# IRC2K16.net
KiCad netlist of a schematic drawn in EAGLE
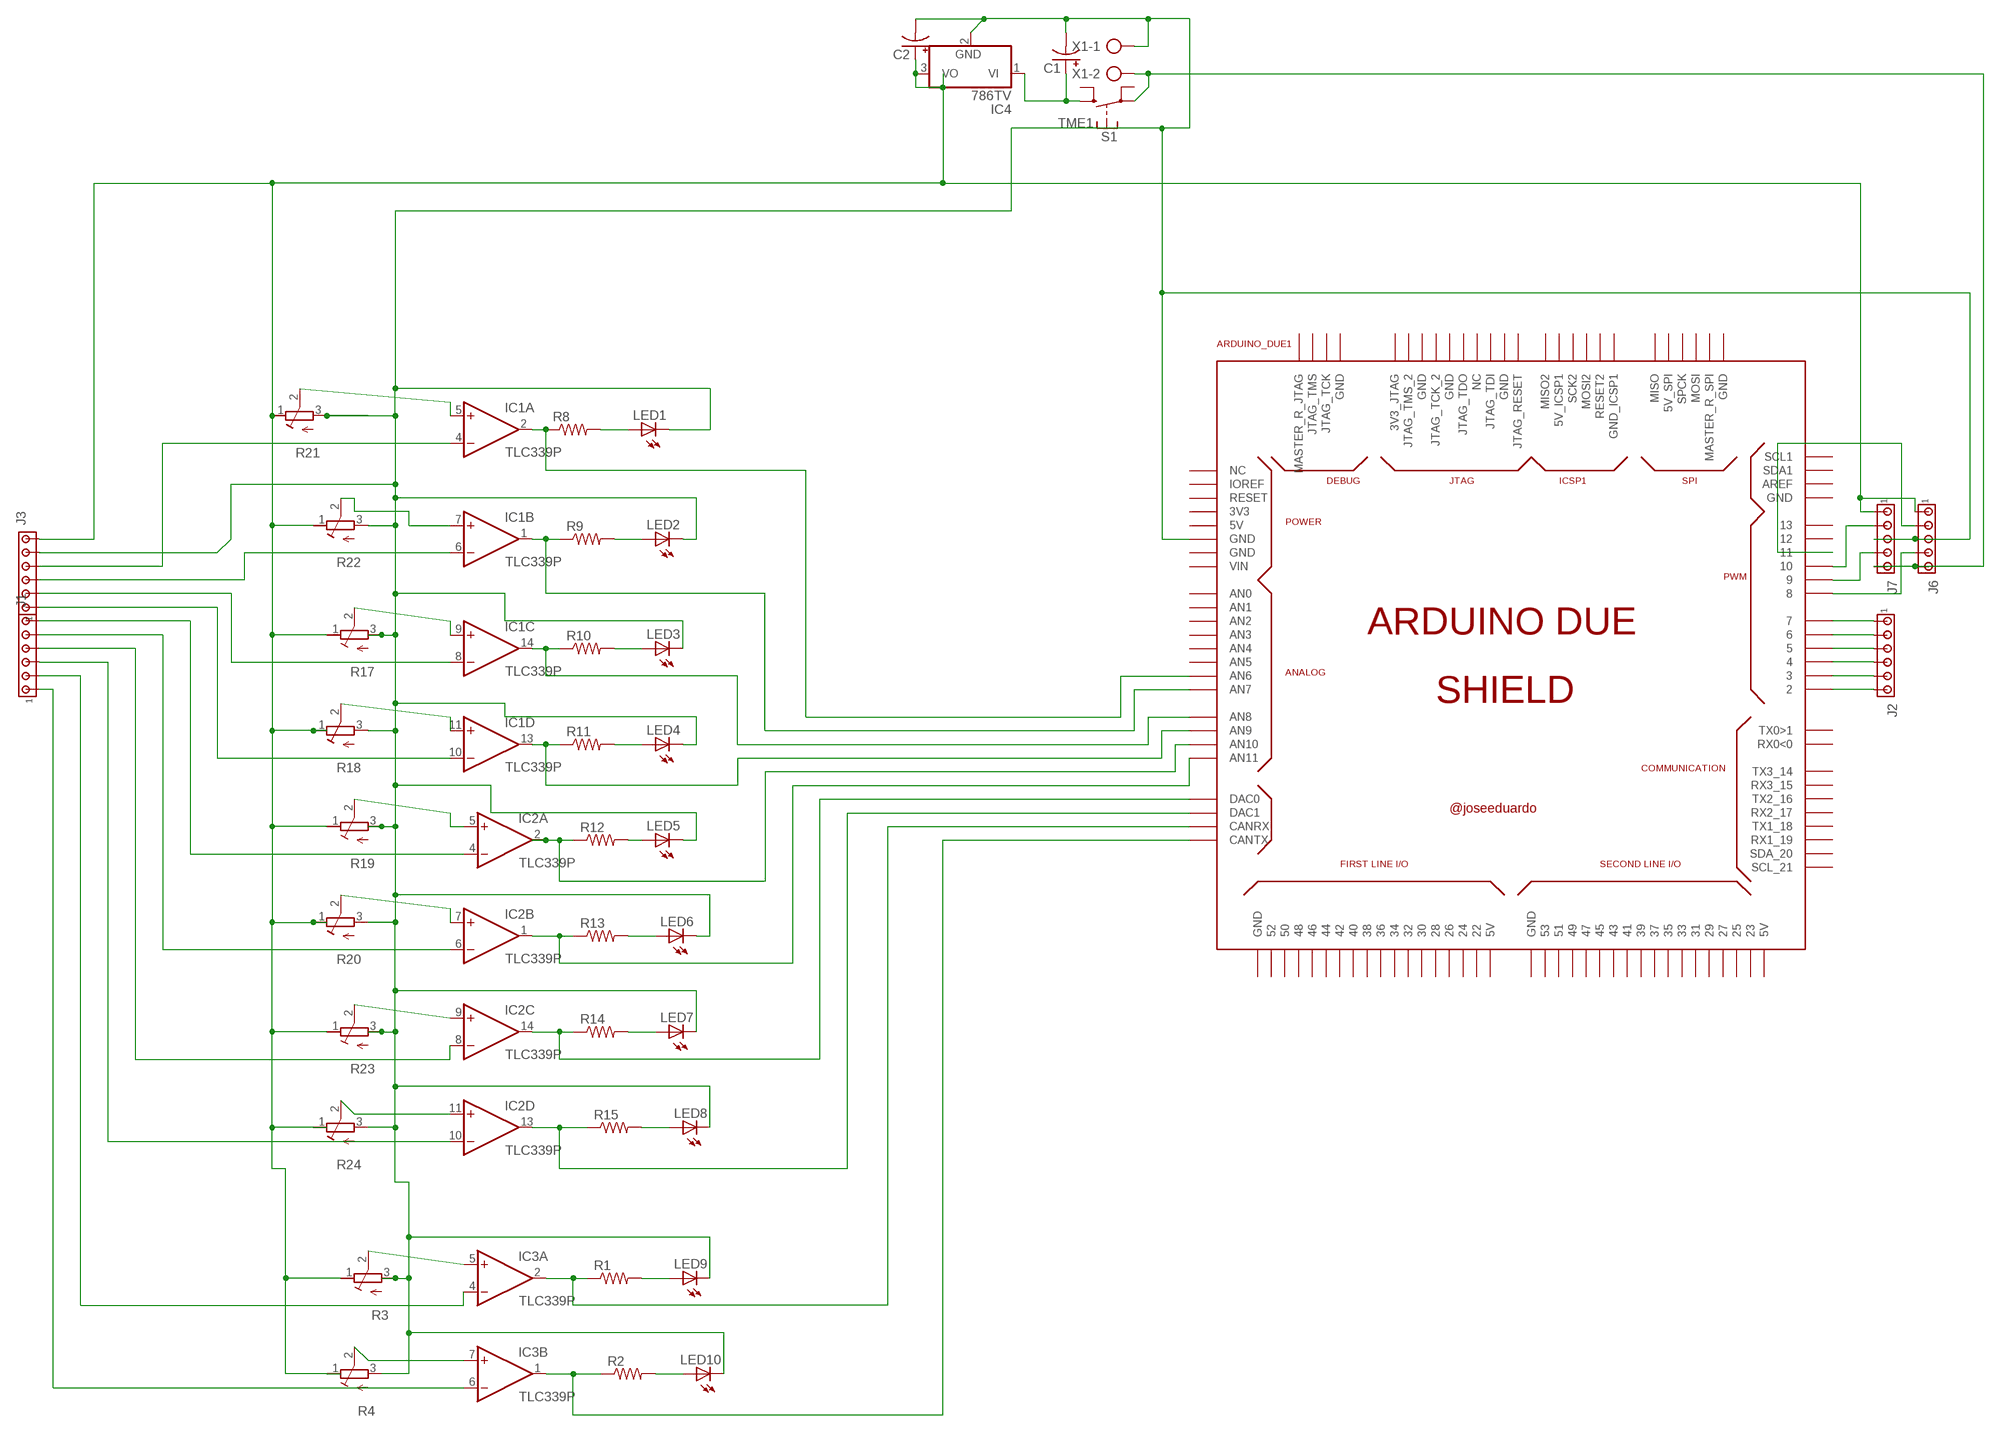
[diagram p0: schematic, sheet 1]

(export (version "E")
  (design (tool "Eeschema 10.0.6"))
  (components
    (comp (ref "ARDUINO_DUE1")
      (value "ARDUINO_DUE_SHIELD")
      (footprint "eagle-import:ARDUINO_DUE_SHIELD")
      (libsource (lib "eagle-import") (part "ARDUINO_DUE_SHIELD"))
    )
    (comp (ref "C1")
      (value "CPOL-USE5-10.5")
      (footprint "eagle-import:E5-10,5")
      (libsource (lib "eagle-import") (part "CPOL-USE5-10.5"))
    )
    (comp (ref "C2")
      (value "CPOL-USE5-10.5")
      (footprint "eagle-import:E5-10,5")
      (libsource (lib "eagle-import") (part "CPOL-USE5-10.5"))
    )
    (comp (ref "IC1")
      (value "TLC339P")
      (footprint "eagle-import:DIL14")
      (libsource (lib "eagle-import") (part "TLC339P"))
    )
    (comp (ref "IC2")
      (value "TLC339P")
      (footprint "eagle-import:DIL14")
      (libsource (lib "eagle-import") (part "TLC339P"))
    )
    (comp (ref "IC3")
      (value "TLC339P")
      (footprint "eagle-import:DIL14")
      (libsource (lib "eagle-import") (part "TLC339P"))
    )
    (comp (ref "IC4")
      (value "786TV")
      (footprint "eagle-import:TO220V")
      (libsource (lib "eagle-import") (part "78TV6"))
    )
    (comp (ref "J1")
      (value "MTA06-100")
      (footprint "eagle-import:10X06MTA")
      (libsource (lib "eagle-import") (part "MTA06-100"))
    )
    (comp (ref "J2")
      (value "MTA06-100")
      (footprint "eagle-import:10X06MTA")
      (libsource (lib "eagle-import") (part "MTA06-100"))
    )
    (comp (ref "J3")
      (value "MTA06-100")
      (footprint "eagle-import:10X06MTA")
      (libsource (lib "eagle-import") (part "MTA06-100"))
    )
    (comp (ref "J6")
      (value "MTA05-100")
      (footprint "eagle-import:10X05MTA")
      (libsource (lib "eagle-import") (part "MTA05-100"))
    )
    (comp (ref "J7")
      (value "MTA05-100")
      (footprint "eagle-import:10X05MTA")
      (libsource (lib "eagle-import") (part "MTA05-100"))
    )
    (comp (ref "LED1")
      (value "LED3MM")
      (footprint "eagle-import:LED3MM")
      (libsource (lib "eagle-import") (part "LED3MM"))
    )
    (comp (ref "LED2")
      (value "LED3MM")
      (footprint "eagle-import:LED3MM")
      (libsource (lib "eagle-import") (part "LED3MM"))
    )
    (comp (ref "LED3")
      (value "LED3MM")
      (footprint "eagle-import:LED3MM")
      (libsource (lib "eagle-import") (part "LED3MM"))
    )
    (comp (ref "LED4")
      (value "LED3MM")
      (footprint "eagle-import:LED3MM")
      (libsource (lib "eagle-import") (part "LED3MM"))
    )
    (comp (ref "LED5")
      (value "LED3MM")
      (footprint "eagle-import:LED3MM")
      (libsource (lib "eagle-import") (part "LED3MM"))
    )
    (comp (ref "LED6")
      (value "LED3MM")
      (footprint "eagle-import:LED3MM")
      (libsource (lib "eagle-import") (part "LED3MM"))
    )
    (comp (ref "LED7")
      (value "LED3MM")
      (footprint "eagle-import:LED3MM")
      (libsource (lib "eagle-import") (part "LED3MM"))
    )
    (comp (ref "LED8")
      (value "LED3MM")
      (footprint "eagle-import:LED3MM")
      (libsource (lib "eagle-import") (part "LED3MM"))
    )
    (comp (ref "LED9")
      (value "LED3MM")
      (footprint "eagle-import:LED3MM")
      (libsource (lib "eagle-import") (part "LED3MM"))
    )
    (comp (ref "LED10")
      (value "LED3MM")
      (footprint "eagle-import:LED3MM")
      (libsource (lib "eagle-import") (part "LED3MM"))
    )
    (comp (ref "R1")
      (value "R-US_0207/10")
      (footprint "eagle-import:0207_10")
      (libsource (lib "eagle-import") (part "R-US_0207/10"))
    )
    (comp (ref "R2")
      (value "R-US_0207/10")
      (footprint "eagle-import:0207_10")
      (libsource (lib "eagle-import") (part "R-US_0207/10"))
    )
    (comp (ref "R3")
      (value "R-TRIMMT93YA")
      (footprint "eagle-import:RTRIMT93YA")
      (libsource (lib "eagle-import") (part "R-TRIMMT93YA"))
    )
    (comp (ref "R4")
      (value "R-TRIMMT93YA")
      (footprint "eagle-import:RTRIMT93YA")
      (libsource (lib "eagle-import") (part "R-TRIMMT93YA"))
    )
    (comp (ref "R8")
      (value "R-US_0207/10")
      (footprint "eagle-import:0207_10")
      (libsource (lib "eagle-import") (part "R-US_0207/10"))
    )
    (comp (ref "R9")
      (value "R-US_0207/10")
      (footprint "eagle-import:0207_10")
      (libsource (lib "eagle-import") (part "R-US_0207/10"))
    )
    (comp (ref "R10")
      (value "R-US_0207/10")
      (footprint "eagle-import:0207_10")
      (libsource (lib "eagle-import") (part "R-US_0207/10"))
    )
    (comp (ref "R11")
      (value "R-US_0207/10")
      (footprint "eagle-import:0207_10")
      (libsource (lib "eagle-import") (part "R-US_0207/10"))
    )
    (comp (ref "R12")
      (value "R-US_0207/10")
      (footprint "eagle-import:0207_10")
      (libsource (lib "eagle-import") (part "R-US_0207/10"))
    )
    (comp (ref "R13")
      (value "R-US_0207/10")
      (footprint "eagle-import:0207_10")
      (libsource (lib "eagle-import") (part "R-US_0207/10"))
    )
    (comp (ref "R14")
      (value "R-US_0207/10")
      (footprint "eagle-import:0207_10")
      (libsource (lib "eagle-import") (part "R-US_0207/10"))
    )
    (comp (ref "R15")
      (value "R-US_0207/10")
      (footprint "eagle-import:0207_10")
      (libsource (lib "eagle-import") (part "R-US_0207/10"))
    )
    (comp (ref "R17")
      (value "R-TRIMMT93YA")
      (footprint "eagle-import:RTRIMT93YA")
      (libsource (lib "eagle-import") (part "R-TRIMMT93YA"))
    )
    (comp (ref "R18")
      (value "R-TRIMMT93YA")
      (footprint "eagle-import:RTRIMT93YA")
      (libsource (lib "eagle-import") (part "R-TRIMMT93YA"))
    )
    (comp (ref "R19")
      (value "R-TRIMMT93YA")
      (footprint "eagle-import:RTRIMT93YA")
      (libsource (lib "eagle-import") (part "R-TRIMMT93YA"))
    )
    (comp (ref "R20")
      (value "R-TRIMMT93YA")
      (footprint "eagle-import:RTRIMT93YA")
      (libsource (lib "eagle-import") (part "R-TRIMMT93YA"))
    )
    (comp (ref "R21")
      (value "R-TRIMMT93YA")
      (footprint "eagle-import:RTRIMT93YA")
      (libsource (lib "eagle-import") (part "R-TRIMMT93YA"))
    )
    (comp (ref "R22")
      (value "R-TRIMMT93YA")
      (footprint "eagle-import:RTRIMT93YA")
      (libsource (lib "eagle-import") (part "R-TRIMMT93YA"))
    )
    (comp (ref "R23")
      (value "R-TRIMMT93YA")
      (footprint "eagle-import:RTRIMT93YA")
      (libsource (lib "eagle-import") (part "R-TRIMMT93YA"))
    )
    (comp (ref "R24")
      (value "R-TRIMMT93YA")
      (footprint "eagle-import:RTRIMT93YA")
      (libsource (lib "eagle-import") (part "R-TRIMMT93YA"))
    )
    (comp (ref "S1")
      (value "TME1")
      (footprint "eagle-import:TME1")
      (libsource (lib "eagle-import") (part "TME1"))
    )
    (comp (ref "X1")
      (value "AK300/2")
      (footprint "eagle-import:AK300_2")
      (libsource (lib "eagle-import") (part "AK300/2"))
    )
  )
  (nets
    (net (code "1") (name "Net-(ARDUINO_DUE1-AN6)") (class "Default")
      (node (ref "ARDUINO_DUE1") (pin "A6") (pinfunction "AN6_A6") (pintype "bidirectional"))
      (node (ref "IC1") (pin "2") (pinfunction "OUT_2") (pintype "output"))
      (node (ref "R8") (pin "1") (pinfunction "1_1") (pintype "passive"))
    )
    (net (code "2") (name "Net-(ARDUINO_DUE1-AN7)") (class "Default")
      (node (ref "ARDUINO_DUE1") (pin "A7") (pinfunction "AN7_A7") (pintype "bidirectional"))
      (node (ref "IC1") (pin "1") (pinfunction "OUT_1") (pintype "output"))
      (node (ref "R9") (pin "1") (pinfunction "1_1") (pintype "passive"))
    )
    (net (code "3") (name "Net-(ARDUINO_DUE1-AN8)") (class "Default")
      (node (ref "ARDUINO_DUE1") (pin "A8") (pinfunction "AN8_A8") (pintype "bidirectional"))
      (node (ref "IC1") (pin "14") (pinfunction "OUT_14") (pintype "output"))
      (node (ref "R10") (pin "1") (pinfunction "1_1") (pintype "passive"))
    )
    (net (code "4") (name "Net-(ARDUINO_DUE1-AN9)") (class "Default")
      (node (ref "ARDUINO_DUE1") (pin "A9") (pinfunction "AN9_A9") (pintype "bidirectional"))
      (node (ref "IC1") (pin "13") (pinfunction "OUT_13") (pintype "output"))
      (node (ref "R11") (pin "1") (pinfunction "1_1") (pintype "passive"))
    )
    (net (code "5") (name "Net-(ARDUINO_DUE1-AN10)") (class "Default")
      (node (ref "ARDUINO_DUE1") (pin "A10") (pinfunction "AN10_A10") (pintype "bidirectional"))
      (node (ref "IC2") (pin "2") (pinfunction "OUT_2") (pintype "output"))
      (node (ref "R12") (pin "1") (pinfunction "1_1") (pintype "passive"))
    )
    (net (code "6") (name "Net-(ARDUINO_DUE1-AN11)") (class "Default")
      (node (ref "ARDUINO_DUE1") (pin "A11") (pinfunction "AN11_A11") (pintype "bidirectional"))
      (node (ref "IC2") (pin "1") (pinfunction "OUT_1") (pintype "output"))
      (node (ref "R13") (pin "1") (pinfunction "1_1") (pintype "passive"))
    )
    (net (code "7") (name "Net-(ARDUINO_DUE1-Pad8)") (class "Default")
      (node (ref "ARDUINO_DUE1") (pin "8") (pinfunction "8_8") (pintype "bidirectional"))
      (node (ref "J6") (pin "4") (pinfunction "4_4") (pintype "passive"))
    )
    (net (code "8") (name "Net-(ARDUINO_DUE1-Pad9)") (class "Default")
      (node (ref "ARDUINO_DUE1") (pin "9") (pinfunction "9_9") (pintype "bidirectional"))
      (node (ref "J7") (pin "4") (pinfunction "4_4") (pintype "passive"))
    )
    (net (code "9") (name "Net-(ARDUINO_DUE1-Pad10)") (class "Default")
      (node (ref "ARDUINO_DUE1") (pin "10") (pinfunction "10_10") (pintype "bidirectional"))
      (node (ref "J7") (pin "2") (pinfunction "2_2") (pintype "passive"))
    )
    (net (code "10") (name "Net-(ARDUINO_DUE1-Pad11)") (class "Default")
      (node (ref "ARDUINO_DUE1") (pin "11") (pinfunction "11_11") (pintype "bidirectional"))
      (node (ref "J6") (pin "2") (pinfunction "2_2") (pintype "passive"))
    )
    (net (code "11") (name "Net-(IC1A-+IN)") (class "Default")
      (node (ref "IC1") (pin "5") (pinfunction "+IN_5") (pintype "input"))
      (node (ref "R21") (pin "2") (pinfunction "S_2") (pintype "passive"))
    )
    (net (code "12") (name "Net-(IC1A--IN)") (class "Default")
      (node (ref "IC1") (pin "4") (pinfunction "-IN_4") (pintype "input"))
      (node (ref "J3") (pin "3") (pinfunction "4_3") (pintype "passive"))
    )
    (net (code "13") (name "Net-(IC1B-+IN)") (class "Default")
      (node (ref "IC1") (pin "7") (pinfunction "+IN_7") (pintype "input"))
      (node (ref "R22") (pin "2") (pinfunction "S_2") (pintype "passive"))
    )
    (net (code "14") (name "Net-(IC1B--IN)") (class "Default")
      (node (ref "IC1") (pin "6") (pinfunction "-IN_6") (pintype "input"))
      (node (ref "J3") (pin "4") (pinfunction "3_4") (pintype "passive"))
    )
    (net (code "15") (name "Net-(IC1C-+IN)") (class "Default")
      (node (ref "IC1") (pin "9") (pinfunction "+IN_9") (pintype "input"))
      (node (ref "R17") (pin "2") (pinfunction "S_2") (pintype "passive"))
    )
    (net (code "16") (name "Net-(IC1C--IN)") (class "Default")
      (node (ref "IC1") (pin "8") (pinfunction "-IN_8") (pintype "input"))
      (node (ref "J3") (pin "5") (pinfunction "2_5") (pintype "passive"))
    )
    (net (code "17") (name "Net-(IC1D-+IN)") (class "Default")
      (node (ref "IC1") (pin "11") (pinfunction "+IN_11") (pintype "input"))
      (node (ref "R18") (pin "2") (pinfunction "S_2") (pintype "passive"))
    )
    (net (code "18") (name "Net-(IC1D--IN)") (class "Default")
      (node (ref "IC1") (pin "10") (pinfunction "-IN_10") (pintype "input"))
      (node (ref "J3") (pin "6") (pinfunction "1_6") (pintype "passive"))
    )
    (net (code "19") (name "Net-(IC2A-+IN)") (class "Default")
      (node (ref "IC2") (pin "5") (pinfunction "+IN_5") (pintype "input"))
      (node (ref "R19") (pin "2") (pinfunction "S_2") (pintype "passive"))
    )
    (net (code "20") (name "Net-(IC2A--IN)") (class "Default")
      (node (ref "IC2") (pin "4") (pinfunction "-IN_4") (pintype "input"))
      (node (ref "J1") (pin "1") (pinfunction "6_1") (pintype "passive"))
    )
    (net (code "21") (name "Net-(IC2B-+IN)") (class "Default")
      (node (ref "IC2") (pin "7") (pinfunction "+IN_7") (pintype "input"))
      (node (ref "R20") (pin "2") (pinfunction "S_2") (pintype "passive"))
    )
    (net (code "22") (name "Net-(IC2B--IN)") (class "Default")
      (node (ref "IC2") (pin "6") (pinfunction "-IN_6") (pintype "input"))
      (node (ref "J1") (pin "2") (pinfunction "5_2") (pintype "passive"))
    )
    (net (code "23") (name "Net-(IC2C-+IN)") (class "Default")
      (node (ref "IC2") (pin "9") (pinfunction "+IN_9") (pintype "input"))
      (node (ref "R23") (pin "2") (pinfunction "S_2") (pintype "passive"))
    )
    (net (code "24") (name "Net-(IC2C--IN)") (class "Default")
      (node (ref "IC2") (pin "8") (pinfunction "-IN_8") (pintype "input"))
      (node (ref "J1") (pin "3") (pinfunction "4_3") (pintype "passive"))
    )
    (net (code "25") (name "Net-(IC2C-OUT)") (class "Default")
      (node (ref "ARDUINO_DUE1") (pin "DAC0") (pinfunction "DAC0_DAC0") (pintype "bidirectional"))
      (node (ref "IC2") (pin "14") (pinfunction "OUT_14") (pintype "output"))
      (node (ref "R14") (pin "1") (pinfunction "1_1") (pintype "passive"))
    )
    (net (code "26") (name "Net-(IC2D-+IN)") (class "Default")
      (node (ref "IC2") (pin "11") (pinfunction "+IN_11") (pintype "input"))
      (node (ref "R24") (pin "2") (pinfunction "S_2") (pintype "passive"))
    )
    (net (code "27") (name "Net-(IC2D--IN)") (class "Default")
      (node (ref "IC2") (pin "10") (pinfunction "-IN_10") (pintype "input"))
      (node (ref "J1") (pin "4") (pinfunction "3_4") (pintype "passive"))
    )
    (net (code "28") (name "Net-(IC2D-OUT)") (class "Default")
      (node (ref "ARDUINO_DUE1") (pin "DAC1") (pinfunction "DAC1_DAC1") (pintype "bidirectional"))
      (node (ref "IC2") (pin "13") (pinfunction "OUT_13") (pintype "output"))
      (node (ref "R15") (pin "1") (pinfunction "1_1") (pintype "passive"))
    )
    (net (code "29") (name "Net-(IC3A-+IN)") (class "Default")
      (node (ref "IC3") (pin "5") (pinfunction "+IN_5") (pintype "input"))
      (node (ref "R3") (pin "2") (pinfunction "S_2") (pintype "passive"))
    )
    (net (code "30") (name "Net-(IC3A--IN)") (class "Default")
      (node (ref "IC3") (pin "4") (pinfunction "-IN_4") (pintype "input"))
      (node (ref "J1") (pin "5") (pinfunction "2_5") (pintype "passive"))
    )
    (net (code "31") (name "Net-(IC3A-OUT)") (class "Default")
      (node (ref "ARDUINO_DUE1") (pin "CANRX") (pinfunction "CANRX_CANRX") (pintype "bidirectional"))
      (node (ref "IC3") (pin "2") (pinfunction "OUT_2") (pintype "output"))
      (node (ref "R1") (pin "1") (pinfunction "1_1") (pintype "passive"))
    )
    (net (code "32") (name "Net-(IC3B-+IN)") (class "Default")
      (node (ref "IC3") (pin "7") (pinfunction "+IN_7") (pintype "input"))
      (node (ref "R4") (pin "2") (pinfunction "S_2") (pintype "passive"))
    )
    (net (code "33") (name "Net-(IC3B--IN)") (class "Default")
      (node (ref "IC3") (pin "6") (pinfunction "-IN_6") (pintype "input"))
      (node (ref "J1") (pin "6") (pinfunction "1_6") (pintype "passive"))
    )
    (net (code "34") (name "Net-(IC3B-OUT)") (class "Default")
      (node (ref "ARDUINO_DUE1") (pin "CANTX") (pinfunction "CANTX_CANTX") (pintype "bidirectional"))
      (node (ref "IC3") (pin "1") (pinfunction "OUT_1") (pintype "output"))
      (node (ref "R2") (pin "1") (pinfunction "1_1") (pintype "passive"))
    )
    (net (code "35") (name "Net-(IC4-GND)") (class "Default")
      (node (ref "ARDUINO_DUE1") (pin "GND") (pinfunction "GND_GND") (pintype "bidirectional"))
      (node (ref "C1") (pin "-") (pinfunction "-_-") (pintype "passive"))
      (node (ref "C2") (pin "-") (pinfunction "-_-") (pintype "passive"))
      (node (ref "IC4") (pin "2") (pinfunction "GND_2") (pintype "passive"))
      (node (ref "J3") (pin "2") (pinfunction "5_2") (pintype "passive"))
      (node (ref "J6") (pin "3") (pinfunction "3_3") (pintype "passive"))
      (node (ref "J7") (pin "3") (pinfunction "3_3") (pintype "passive"))
      (node (ref "LED1") (pin "K") (pinfunction "C_K") (pintype "passive"))
      (node (ref "LED10") (pin "K") (pinfunction "C_K") (pintype "passive"))
      (node (ref "LED2") (pin "K") (pinfunction "C_K") (pintype "passive"))
      (node (ref "LED3") (pin "K") (pinfunction "C_K") (pintype "passive"))
      (node (ref "LED4") (pin "K") (pinfunction "C_K") (pintype "passive"))
      (node (ref "LED5") (pin "K") (pinfunction "C_K") (pintype "passive"))
      (node (ref "LED6") (pin "K") (pinfunction "C_K") (pintype "passive"))
      (node (ref "LED7") (pin "K") (pinfunction "C_K") (pintype "passive"))
      (node (ref "LED8") (pin "K") (pinfunction "C_K") (pintype "passive"))
      (node (ref "LED9") (pin "K") (pinfunction "C_K") (pintype "passive"))
      (node (ref "R17") (pin "3") (pinfunction "E_3") (pintype "passive"))
      (node (ref "R18") (pin "3") (pinfunction "E_3") (pintype "passive"))
      (node (ref "R19") (pin "3") (pinfunction "E_3") (pintype "passive"))
      (node (ref "R20") (pin "3") (pinfunction "E_3") (pintype "passive"))
      (node (ref "R21") (pin "3") (pinfunction "E_3") (pintype "passive"))
      (node (ref "R22") (pin "3") (pinfunction "E_3") (pintype "passive"))
      (node (ref "R23") (pin "3") (pinfunction "E_3") (pintype "passive"))
      (node (ref "R24") (pin "3") (pinfunction "E_3") (pintype "passive"))
      (node (ref "R3") (pin "3") (pinfunction "E_3") (pintype "passive"))
      (node (ref "R4") (pin "3") (pinfunction "E_3") (pintype "passive"))
      (node (ref "X1") (pin "1") (pinfunction "KL_1") (pintype "passive"))
    )
    (net (code "36") (name "Net-(IC4-VI)") (class "Default")
      (node (ref "C1") (pin "+") (pinfunction "+_+") (pintype "passive"))
      (node (ref "IC4") (pin "1") (pinfunction "VI_1") (pintype "input"))
      (node (ref "S1") (pin "1") (pinfunction "S_1") (pintype "passive"))
    )
    (net (code "37") (name "Net-(IC4-VO)") (class "Default")
      (node (ref "C2") (pin "+") (pinfunction "+_+") (pintype "passive"))
      (node (ref "IC4") (pin "3") (pinfunction "VO_3") (pintype "passive"))
      (node (ref "J3") (pin "1") (pinfunction "6_1") (pintype "passive"))
      (node (ref "J6") (pin "1") (pinfunction "1_1") (pintype "passive"))
      (node (ref "J7") (pin "1") (pinfunction "1_1") (pintype "passive"))
      (node (ref "R17") (pin "1") (pinfunction "A_1") (pintype "passive"))
      (node (ref "R18") (pin "1") (pinfunction "A_1") (pintype "passive"))
      (node (ref "R19") (pin "1") (pinfunction "A_1") (pintype "passive"))
      (node (ref "R20") (pin "1") (pinfunction "A_1") (pintype "passive"))
      (node (ref "R21") (pin "1") (pinfunction "A_1") (pintype "passive"))
      (node (ref "R22") (pin "1") (pinfunction "A_1") (pintype "passive"))
      (node (ref "R23") (pin "1") (pinfunction "A_1") (pintype "passive"))
      (node (ref "R24") (pin "1") (pinfunction "A_1") (pintype "passive"))
      (node (ref "R3") (pin "1") (pinfunction "A_1") (pintype "passive"))
      (node (ref "R4") (pin "1") (pinfunction "A_1") (pintype "passive"))
    )
    (net (code "38") (name "Net-(J2-1)") (class "Default")
      (node (ref "ARDUINO_DUE1") (pin "7") (pinfunction "7_7") (pintype "bidirectional"))
      (node (ref "J2") (pin "6") (pinfunction "1_6") (pintype "passive"))
    )
    (net (code "39") (name "Net-(J2-2)") (class "Default")
      (node (ref "ARDUINO_DUE1") (pin "6") (pinfunction "6_6") (pintype "bidirectional"))
      (node (ref "J2") (pin "5") (pinfunction "2_5") (pintype "passive"))
    )
    (net (code "40") (name "Net-(J2-3)") (class "Default")
      (node (ref "ARDUINO_DUE1") (pin "5") (pinfunction "5_5") (pintype "bidirectional"))
      (node (ref "J2") (pin "4") (pinfunction "3_4") (pintype "passive"))
    )
    (net (code "41") (name "Net-(J2-4)") (class "Default")
      (node (ref "ARDUINO_DUE1") (pin "4") (pinfunction "4_4") (pintype "bidirectional"))
      (node (ref "J2") (pin "3") (pinfunction "4_3") (pintype "passive"))
    )
    (net (code "42") (name "Net-(J2-5)") (class "Default")
      (node (ref "ARDUINO_DUE1") (pin "3") (pinfunction "3_3") (pintype "bidirectional"))
      (node (ref "J2") (pin "2") (pinfunction "5_2") (pintype "passive"))
    )
    (net (code "43") (name "Net-(J2-6)") (class "Default")
      (node (ref "ARDUINO_DUE1") (pin "2") (pinfunction "2_2") (pintype "bidirectional"))
      (node (ref "J2") (pin "1") (pinfunction "6_1") (pintype "passive"))
    )
    (net (code "44") (name "Net-(LED1-PadA)") (class "Default")
      (node (ref "LED1") (pin "A") (pinfunction "A_A") (pintype "passive"))
      (node (ref "R8") (pin "2") (pinfunction "2_2") (pintype "passive"))
    )
    (net (code "45") (name "Net-(LED2-PadA)") (class "Default")
      (node (ref "LED2") (pin "A") (pinfunction "A_A") (pintype "passive"))
      (node (ref "R9") (pin "2") (pinfunction "2_2") (pintype "passive"))
    )
    (net (code "46") (name "Net-(LED3-PadA)") (class "Default")
      (node (ref "LED3") (pin "A") (pinfunction "A_A") (pintype "passive"))
      (node (ref "R10") (pin "2") (pinfunction "2_2") (pintype "passive"))
    )
    (net (code "47") (name "Net-(LED4-PadA)") (class "Default")
      (node (ref "LED4") (pin "A") (pinfunction "A_A") (pintype "passive"))
      (node (ref "R11") (pin "2") (pinfunction "2_2") (pintype "passive"))
    )
    (net (code "48") (name "Net-(LED5-PadA)") (class "Default")
      (node (ref "LED5") (pin "A") (pinfunction "A_A") (pintype "passive"))
      (node (ref "R12") (pin "2") (pinfunction "2_2") (pintype "passive"))
    )
    (net (code "49") (name "Net-(LED6-PadA)") (class "Default")
      (node (ref "LED6") (pin "A") (pinfunction "A_A") (pintype "passive"))
      (node (ref "R13") (pin "2") (pinfunction "2_2") (pintype "passive"))
    )
    (net (code "50") (name "Net-(LED7-PadA)") (class "Default")
      (node (ref "LED7") (pin "A") (pinfunction "A_A") (pintype "passive"))
      (node (ref "R14") (pin "2") (pinfunction "2_2") (pintype "passive"))
    )
    (net (code "51") (name "Net-(LED8-PadA)") (class "Default")
      (node (ref "LED8") (pin "A") (pinfunction "A_A") (pintype "passive"))
      (node (ref "R15") (pin "2") (pinfunction "2_2") (pintype "passive"))
    )
    (net (code "52") (name "Net-(LED9-PadA)") (class "Default")
      (node (ref "LED9") (pin "A") (pinfunction "A_A") (pintype "passive"))
      (node (ref "R1") (pin "2") (pinfunction "2_2") (pintype "passive"))
    )
    (net (code "53") (name "Net-(LED10-PadA)") (class "Default")
      (node (ref "LED10") (pin "A") (pinfunction "A_A") (pintype "passive"))
      (node (ref "R2") (pin "2") (pinfunction "2_2") (pintype "passive"))
    )
    (net (code "54") (name "Net-(X1B-KL)") (class "Default")
      (node (ref "J6") (pin "5") (pinfunction "5_5") (pintype "passive"))
      (node (ref "J7") (pin "5") (pinfunction "5_5") (pintype "passive"))
      (node (ref "S1") (pin "2") (pinfunction "P_2") (pintype "passive"))
      (node (ref "X1") (pin "2") (pinfunction "KL_2") (pintype "passive"))
    )
    (net (code "55") (name "unconnected-(ARDUINO_DUE1-5V-Pad5V0)") (class "Default")
      (node (ref "ARDUINO_DUE1") (pin "5V0") (pinfunction "5V_5V0") (pintype "bidirectional"))
    )
    (net (code "56") (name "unconnected-(ARDUINO_DUE1-5V-Pad5V0_1)") (class "Default")
      (node (ref "ARDUINO_DUE1") (pin "5V0_1") (pinfunction "5V_5V0_1") (pintype "bidirectional"))
    )
    (net (code "57") (name "unconnected-(ARDUINO_DUE1-5V-Pad5V0_2)") (class "Default")
      (node (ref "ARDUINO_DUE1") (pin "5V0_2") (pinfunction "5V_5V0_2") (pintype "bidirectional"))
    )
    (net (code "58") (name "unconnected-(ARDUINO_DUE1-5V_SPI-Pad5V_2)") (class "Default")
      (node (ref "ARDUINO_DUE1") (pin "5V_2") (pinfunction "5V_SPI_5V_2") (pintype "bidirectional"))
    )
    (net (code "59") (name "unconnected-(ARDUINO_DUE1-AN0-PadA0)") (class "Default")
      (node (ref "ARDUINO_DUE1") (pin "A0") (pinfunction "AN0_A0") (pintype "bidirectional"))
    )
    (net (code "60") (name "unconnected-(ARDUINO_DUE1-AN1-PadA1)") (class "Default")
      (node (ref "ARDUINO_DUE1") (pin "A1") (pinfunction "AN1_A1") (pintype "bidirectional"))
    )
    (net (code "61") (name "unconnected-(ARDUINO_DUE1-AN2-PadA2)") (class "Default")
      (node (ref "ARDUINO_DUE1") (pin "A2") (pinfunction "AN2_A2") (pintype "bidirectional"))
    )
    (net (code "62") (name "unconnected-(ARDUINO_DUE1-AN3-PadA3)") (class "Default")
      (node (ref "ARDUINO_DUE1") (pin "A3") (pinfunction "AN3_A3") (pintype "bidirectional"))
    )
    (net (code "63") (name "unconnected-(ARDUINO_DUE1-AN4-PadA4)") (class "Default")
      (node (ref "ARDUINO_DUE1") (pin "A4") (pinfunction "AN4_A4") (pintype "bidirectional"))
    )
    (net (code "64") (name "unconnected-(ARDUINO_DUE1-AN5-PadA5)") (class "Default")
      (node (ref "ARDUINO_DUE1") (pin "A5") (pinfunction "AN5_A5") (pintype "bidirectional"))
    )
    (net (code "65") (name "unconnected-(ARDUINO_DUE1-GND-PadGND_1)") (class "Default")
      (node (ref "ARDUINO_DUE1") (pin "GND_1") (pinfunction "GND_GND_1") (pintype "bidirectional"))
    )
    (net (code "66") (name "unconnected-(ARDUINO_DUE1-GND-PadGND_2)") (class "Default")
      (node (ref "ARDUINO_DUE1") (pin "GND_2") (pinfunction "GND_GND_2") (pintype "bidirectional"))
    )
    (net (code "67") (name "unconnected-(ARDUINO_DUE1-GND-PadGND_3)") (class "Default")
      (node (ref "ARDUINO_DUE1") (pin "GND_3") (pinfunction "GND_GND_3") (pintype "bidirectional"))
    )
    (net (code "68") (name "unconnected-(ARDUINO_DUE1-GND-PadGND_4)") (class "Default")
      (node (ref "ARDUINO_DUE1") (pin "GND_4") (pinfunction "GND_GND_4") (pintype "bidirectional"))
    )
    (net (code "69") (name "unconnected-(ARDUINO_DUE1-GND-PadGND_5)") (class "Default")
      (node (ref "ARDUINO_DUE1") (pin "GND_5") (pinfunction "GND_GND_5") (pintype "bidirectional"))
    )
    (net (code "70") (name "unconnected-(ARDUINO_DUE1-GND-PadGND_7)") (class "Default")
      (node (ref "ARDUINO_DUE1") (pin "GND_7") (pinfunction "GND_GND_7") (pintype "bidirectional"))
    )
    (net (code "71") (name "unconnected-(ARDUINO_DUE1-GND-PadGND_8)") (class "Default")
      (node (ref "ARDUINO_DUE1") (pin "GND_8") (pinfunction "GND_GND_8") (pintype "bidirectional"))
    )
    (net (code "72") (name "unconnected-(ARDUINO_DUE1-GND-PadGND_9)") (class "Default")
      (node (ref "ARDUINO_DUE1") (pin "GND_9") (pinfunction "GND_GND_9") (pintype "bidirectional"))
    )
    (net (code "73") (name "unconnected-(ARDUINO_DUE1-GND-PadGND_10)") (class "Default")
      (node (ref "ARDUINO_DUE1") (pin "GND_10") (pinfunction "GND_GND_10") (pintype "bidirectional"))
    )
    (net (code "74") (name "unconnected-(ARDUINO_DUE1-MASTER_R_JTAG-PadMASTER_RESET_JTAG)") (class "Default")
      (node (ref "ARDUINO_DUE1") (pin "MASTER_RESET_JTAG") (pinfunction "MASTER_R_JTAG_MASTER_RESET_JTAG") (pintype "bidirectional"))
    )
    (net (code "75") (name "unconnected-(ARDUINO_DUE1-MASTER_R_SPI-PadMASTER_RESET_SPI)") (class "Default")
      (node (ref "ARDUINO_DUE1") (pin "MASTER_RESET_SPI") (pinfunction "MASTER_R_SPI_MASTER_RESET_SPI") (pintype "bidirectional"))
    )
    (net (code "76") (name "unconnected-(ARDUINO_DUE1-NC-PadNC_2)") (class "Default")
      (node (ref "ARDUINO_DUE1") (pin "NC_2") (pinfunction "NC_NC_2") (pintype "no_connect"))
    )
    (net (code "77") (name "unconnected-(ARDUINO_DUE1-NC-PadNC_5)") (class "Default")
      (node (ref "ARDUINO_DUE1") (pin "NC_5") (pinfunction "NC_NC_5") (pintype "bidirectional"))
    )
    (net (code "78") (name "unconnected-(ARDUINO_DUE1-Pad3V3)") (class "Default")
      (node (ref "ARDUINO_DUE1") (pin "3V3") (pinfunction "3V3_3V3") (pintype "bidirectional"))
    )
    (net (code "79") (name "unconnected-(ARDUINO_DUE1-Pad3V3_JTAG)") (class "Default")
      (node (ref "ARDUINO_DUE1") (pin "3V3_JTAG") (pinfunction "3V3_JTAG_3V3_JTAG") (pintype "bidirectional"))
    )
    (net (code "80") (name "unconnected-(ARDUINO_DUE1-Pad5V_ICSP1)") (class "Default")
      (node (ref "ARDUINO_DUE1") (pin "5V_ICSP1") (pinfunction "5V_ICSP1_5V_ICSP1") (pintype "bidirectional"))
    )
    (net (code "81") (name "unconnected-(ARDUINO_DUE1-Pad12)") (class "Default")
      (node (ref "ARDUINO_DUE1") (pin "12") (pinfunction "12_12") (pintype "bidirectional"))
    )
    (net (code "82") (name "unconnected-(ARDUINO_DUE1-Pad13)") (class "Default")
      (node (ref "ARDUINO_DUE1") (pin "13") (pinfunction "13_13") (pintype "bidirectional"))
    )
    (net (code "83") (name "unconnected-(ARDUINO_DUE1-Pad22)") (class "Default")
      (node (ref "ARDUINO_DUE1") (pin "22") (pinfunction "22_22") (pintype "bidirectional"))
    )
    (net (code "84") (name "unconnected-(ARDUINO_DUE1-Pad23)") (class "Default")
      (node (ref "ARDUINO_DUE1") (pin "23") (pinfunction "23_23") (pintype "bidirectional"))
    )
    (net (code "85") (name "unconnected-(ARDUINO_DUE1-Pad24)") (class "Default")
      (node (ref "ARDUINO_DUE1") (pin "24") (pinfunction "24_24") (pintype "bidirectional"))
    )
    (net (code "86") (name "unconnected-(ARDUINO_DUE1-Pad25)") (class "Default")
      (node (ref "ARDUINO_DUE1") (pin "25") (pinfunction "25_25") (pintype "bidirectional"))
    )
    (net (code "87") (name "unconnected-(ARDUINO_DUE1-Pad26)") (class "Default")
      (node (ref "ARDUINO_DUE1") (pin "26") (pinfunction "26_26") (pintype "bidirectional"))
    )
    (net (code "88") (name "unconnected-(ARDUINO_DUE1-Pad27)") (class "Default")
      (node (ref "ARDUINO_DUE1") (pin "27") (pinfunction "27_27") (pintype "bidirectional"))
    )
    (net (code "89") (name "unconnected-(ARDUINO_DUE1-Pad28)") (class "Default")
      (node (ref "ARDUINO_DUE1") (pin "28") (pinfunction "28_28") (pintype "bidirectional"))
    )
    (net (code "90") (name "unconnected-(ARDUINO_DUE1-Pad29)") (class "Default")
      (node (ref "ARDUINO_DUE1") (pin "29") (pinfunction "29_29") (pintype "bidirectional"))
    )
    (net (code "91") (name "unconnected-(ARDUINO_DUE1-Pad30)") (class "Default")
      (node (ref "ARDUINO_DUE1") (pin "30") (pinfunction "30_30") (pintype "bidirectional"))
    )
    (net (code "92") (name "unconnected-(ARDUINO_DUE1-Pad31)") (class "Default")
      (node (ref "ARDUINO_DUE1") (pin "31") (pinfunction "31_31") (pintype "bidirectional"))
    )
    (net (code "93") (name "unconnected-(ARDUINO_DUE1-Pad32)") (class "Default")
      (node (ref "ARDUINO_DUE1") (pin "32") (pinfunction "32_32") (pintype "bidirectional"))
    )
    (net (code "94") (name "unconnected-(ARDUINO_DUE1-Pad33)") (class "Default")
      (node (ref "ARDUINO_DUE1") (pin "33") (pinfunction "33_33") (pintype "bidirectional"))
    )
    (net (code "95") (name "unconnected-(ARDUINO_DUE1-Pad34)") (class "Default")
      (node (ref "ARDUINO_DUE1") (pin "34") (pinfunction "34_34") (pintype "bidirectional"))
    )
    (net (code "96") (name "unconnected-(ARDUINO_DUE1-Pad35)") (class "Default")
      (node (ref "ARDUINO_DUE1") (pin "35") (pinfunction "35_35") (pintype "bidirectional"))
    )
    (net (code "97") (name "unconnected-(ARDUINO_DUE1-Pad36)") (class "Default")
      (node (ref "ARDUINO_DUE1") (pin "36") (pinfunction "36_36") (pintype "bidirectional"))
    )
    (net (code "98") (name "unconnected-(ARDUINO_DUE1-Pad37)") (class "Default")
      (node (ref "ARDUINO_DUE1") (pin "37") (pinfunction "37_37") (pintype "bidirectional"))
    )
    (net (code "99") (name "unconnected-(ARDUINO_DUE1-Pad38)") (class "Default")
      (node (ref "ARDUINO_DUE1") (pin "38") (pinfunction "38_38") (pintype "bidirectional"))
    )
    (net (code "100") (name "unconnected-(ARDUINO_DUE1-Pad39)") (class "Default")
      (node (ref "ARDUINO_DUE1") (pin "39") (pinfunction "39_39") (pintype "bidirectional"))
    )
    (net (code "101") (name "unconnected-(ARDUINO_DUE1-Pad40)") (class "Default")
      (node (ref "ARDUINO_DUE1") (pin "40") (pinfunction "40_40") (pintype "bidirectional"))
    )
    (net (code "102") (name "unconnected-(ARDUINO_DUE1-Pad41)") (class "Default")
      (node (ref "ARDUINO_DUE1") (pin "41") (pinfunction "41_41") (pintype "bidirectional"))
    )
    (net (code "103") (name "unconnected-(ARDUINO_DUE1-Pad42)") (class "Default")
      (node (ref "ARDUINO_DUE1") (pin "42") (pinfunction "42_42") (pintype "bidirectional"))
    )
    (net (code "104") (name "unconnected-(ARDUINO_DUE1-Pad43)") (class "Default")
      (node (ref "ARDUINO_DUE1") (pin "43") (pinfunction "43_43") (pintype "bidirectional"))
    )
    (net (code "105") (name "unconnected-(ARDUINO_DUE1-Pad44)") (class "Default")
      (node (ref "ARDUINO_DUE1") (pin "44") (pinfunction "44_44") (pintype "bidirectional"))
    )
    (net (code "106") (name "unconnected-(ARDUINO_DUE1-Pad45)") (class "Default")
      (node (ref "ARDUINO_DUE1") (pin "45") (pinfunction "45_45") (pintype "bidirectional"))
    )
    (net (code "107") (name "unconnected-(ARDUINO_DUE1-Pad46)") (class "Default")
      (node (ref "ARDUINO_DUE1") (pin "46") (pinfunction "46_46") (pintype "bidirectional"))
    )
    (net (code "108") (name "unconnected-(ARDUINO_DUE1-Pad47)") (class "Default")
      (node (ref "ARDUINO_DUE1") (pin "47") (pinfunction "47_47") (pintype "bidirectional"))
    )
    (net (code "109") (name "unconnected-(ARDUINO_DUE1-Pad48)") (class "Default")
      (node (ref "ARDUINO_DUE1") (pin "48") (pinfunction "48_48") (pintype "bidirectional"))
    )
    (net (code "110") (name "unconnected-(ARDUINO_DUE1-Pad49)") (class "Default")
      (node (ref "ARDUINO_DUE1") (pin "49") (pinfunction "49_49") (pintype "bidirectional"))
    )
    (net (code "111") (name "unconnected-(ARDUINO_DUE1-Pad50)") (class "Default")
      (node (ref "ARDUINO_DUE1") (pin "50") (pinfunction "50_50") (pintype "bidirectional"))
    )
    (net (code "112") (name "unconnected-(ARDUINO_DUE1-Pad51)") (class "Default")
      (node (ref "ARDUINO_DUE1") (pin "51") (pinfunction "51_51") (pintype "bidirectional"))
    )
    (net (code "113") (name "unconnected-(ARDUINO_DUE1-Pad52)") (class "Default")
      (node (ref "ARDUINO_DUE1") (pin "52") (pinfunction "52_52") (pintype "bidirectional"))
    )
    (net (code "114") (name "unconnected-(ARDUINO_DUE1-Pad53)") (class "Default")
      (node (ref "ARDUINO_DUE1") (pin "53") (pinfunction "53_53") (pintype "bidirectional"))
    )
    (net (code "115") (name "unconnected-(ARDUINO_DUE1-PadAREF)") (class "Default")
      (node (ref "ARDUINO_DUE1") (pin "AREF") (pinfunction "AREF_AREF") (pintype "bidirectional"))
    )
    (net (code "116") (name "unconnected-(ARDUINO_DUE1-PadGND_ICSP1)") (class "Default")
      (node (ref "ARDUINO_DUE1") (pin "GND_ICSP1") (pinfunction "GND_ICSP1_GND_ICSP1") (pintype "bidirectional"))
    )
    (net (code "117") (name "unconnected-(ARDUINO_DUE1-PadIOREF)") (class "Default")
      (node (ref "ARDUINO_DUE1") (pin "IOREF") (pinfunction "IOREF_IOREF") (pintype "bidirectional"))
    )
    (net (code "118") (name "unconnected-(ARDUINO_DUE1-PadJTAG_RESET)") (class "Default")
      (node (ref "ARDUINO_DUE1") (pin "JTAG_RESET") (pinfunction "JTAG_RESET_JTAG_RESET") (pintype "bidirectional"))
    )
    (net (code "119") (name "unconnected-(ARDUINO_DUE1-PadJTAG_TCK)") (class "Default")
      (node (ref "ARDUINO_DUE1") (pin "JTAG_TCK") (pinfunction "JTAG_TCK_JTAG_TCK") (pintype "bidirectional"))
    )
    (net (code "120") (name "unconnected-(ARDUINO_DUE1-PadJTAG_TCK_2)") (class "Default")
      (node (ref "ARDUINO_DUE1") (pin "JTAG_TCK_2") (pinfunction "JTAG_TCK_2_JTAG_TCK_2") (pintype "bidirectional"))
    )
    (net (code "121") (name "unconnected-(ARDUINO_DUE1-PadJTAG_TDI)") (class "Default")
      (node (ref "ARDUINO_DUE1") (pin "JTAG_TDI") (pinfunction "JTAG_TDI_JTAG_TDI") (pintype "bidirectional"))
    )
    (net (code "122") (name "unconnected-(ARDUINO_DUE1-PadJTAG_TDO)") (class "Default")
      (node (ref "ARDUINO_DUE1") (pin "JTAG_TDO") (pinfunction "JTAG_TDO_JTAG_TDO") (pintype "bidirectional"))
    )
    (net (code "123") (name "unconnected-(ARDUINO_DUE1-PadJTAG_TMS)") (class "Default")
      (node (ref "ARDUINO_DUE1") (pin "JTAG_TMS") (pinfunction "JTAG_TMS_JTAG_TMS") (pintype "bidirectional"))
    )
    (net (code "124") (name "unconnected-(ARDUINO_DUE1-PadJTAG_TMS_2)") (class "Default")
      (node (ref "ARDUINO_DUE1") (pin "JTAG_TMS_2") (pinfunction "JTAG_TMS_2_JTAG_TMS_2") (pintype "bidirectional"))
    )
    (net (code "125") (name "unconnected-(ARDUINO_DUE1-PadMISO)") (class "Default")
      (node (ref "ARDUINO_DUE1") (pin "MISO") (pinfunction "MISO_MISO") (pintype "bidirectional"))
    )
    (net (code "126") (name "unconnected-(ARDUINO_DUE1-PadMISO2)") (class "Default")
      (node (ref "ARDUINO_DUE1") (pin "MISO2") (pinfunction "MISO2_MISO2") (pintype "bidirectional"))
    )
    (net (code "127") (name "unconnected-(ARDUINO_DUE1-PadMOSI)") (class "Default")
      (node (ref "ARDUINO_DUE1") (pin "MOSI") (pinfunction "MOSI_MOSI") (pintype "bidirectional"))
    )
    (net (code "128") (name "unconnected-(ARDUINO_DUE1-PadMOSI2)") (class "Default")
      (node (ref "ARDUINO_DUE1") (pin "MOSI2") (pinfunction "MOSI2_MOSI2") (pintype "bidirectional"))
    )
    (net (code "129") (name "unconnected-(ARDUINO_DUE1-PadRESET)") (class "Default")
      (node (ref "ARDUINO_DUE1") (pin "RESET") (pinfunction "RESET_RESET") (pintype "bidirectional"))
    )
    (net (code "130") (name "unconnected-(ARDUINO_DUE1-PadRESET2)") (class "Default")
      (node (ref "ARDUINO_DUE1") (pin "RESET2") (pinfunction "RESET2_RESET2") (pintype "bidirectional"))
    )
    (net (code "131") (name "unconnected-(ARDUINO_DUE1-PadSCK2)") (class "Default")
      (node (ref "ARDUINO_DUE1") (pin "SCK2") (pinfunction "SCK2_SCK2") (pintype "bidirectional"))
    )
    (net (code "132") (name "unconnected-(ARDUINO_DUE1-PadSCL1)") (class "Default")
      (node (ref "ARDUINO_DUE1") (pin "SCL1") (pinfunction "SCL1_SCL1") (pintype "bidirectional"))
    )
    (net (code "133") (name "unconnected-(ARDUINO_DUE1-PadSDA1)") (class "Default")
      (node (ref "ARDUINO_DUE1") (pin "SDA1") (pinfunction "SDA1_SDA1") (pintype "bidirectional"))
    )
    (net (code "134") (name "unconnected-(ARDUINO_DUE1-PadSPCK)") (class "Default")
      (node (ref "ARDUINO_DUE1") (pin "SPCK") (pinfunction "SPCK_SPCK") (pintype "bidirectional"))
    )
    (net (code "135") (name "unconnected-(ARDUINO_DUE1-PadVIN)") (class "Default")
      (node (ref "ARDUINO_DUE1") (pin "VIN") (pinfunction "VIN_VIN") (pintype "bidirectional"))
    )
    (net (code "136") (name "unconnected-(ARDUINO_DUE1-RX0<0-Pad0)") (class "Default")
      (node (ref "ARDUINO_DUE1") (pin "0") (pinfunction "RX0<0_0") (pintype "bidirectional"))
    )
    (net (code "137") (name "unconnected-(ARDUINO_DUE1-RX1_19-Pad19)") (class "Default")
      (node (ref "ARDUINO_DUE1") (pin "19") (pinfunction "RX1_19_19") (pintype "bidirectional"))
    )
    (net (code "138") (name "unconnected-(ARDUINO_DUE1-RX2_17-Pad17)") (class "Default")
      (node (ref "ARDUINO_DUE1") (pin "17") (pinfunction "RX2_17_17") (pintype "bidirectional"))
    )
    (net (code "139") (name "unconnected-(ARDUINO_DUE1-RX3_15-Pad15)") (class "Default")
      (node (ref "ARDUINO_DUE1") (pin "15") (pinfunction "RX3_15_15") (pintype "bidirectional"))
    )
    (net (code "140") (name "unconnected-(ARDUINO_DUE1-SCL_21-Pad21)") (class "Default")
      (node (ref "ARDUINO_DUE1") (pin "21") (pinfunction "SCL_21_21") (pintype "bidirectional"))
    )
    (net (code "141") (name "unconnected-(ARDUINO_DUE1-SDA_20-Pad20)") (class "Default")
      (node (ref "ARDUINO_DUE1") (pin "20") (pinfunction "SDA_20_20") (pintype "bidirectional"))
    )
    (net (code "142") (name "unconnected-(ARDUINO_DUE1-TX0>1-Pad1)") (class "Default")
      (node (ref "ARDUINO_DUE1") (pin "1") (pinfunction "TX0>1_1") (pintype "bidirectional"))
    )
    (net (code "143") (name "unconnected-(ARDUINO_DUE1-TX1_18-Pad18)") (class "Default")
      (node (ref "ARDUINO_DUE1") (pin "18") (pinfunction "TX1_18_18") (pintype "bidirectional"))
    )
    (net (code "144") (name "unconnected-(ARDUINO_DUE1-TX2_16-Pad16)") (class "Default")
      (node (ref "ARDUINO_DUE1") (pin "16") (pinfunction "TX2_16_16") (pintype "bidirectional"))
    )
    (net (code "145") (name "unconnected-(ARDUINO_DUE1-TX3_14-Pad14)") (class "Default")
      (node (ref "ARDUINO_DUE1") (pin "14") (pinfunction "TX3_14_14") (pintype "bidirectional"))
    )
    (net (code "146") (name "unconnected-(S1-P-Pad4)") (class "Default")
      (node (ref "S1") (pin "4") (pinfunction "P_4") (pintype "passive"))
    )
    (net (code "147") (name "unconnected-(S1-S-Pad5)") (class "Default")
      (node (ref "S1") (pin "5") (pinfunction "S_5") (pintype "passive"))
    )
  )
)
